# NodeFPGA.net
KiCad netlist of a schematic drawn in Altium Designer
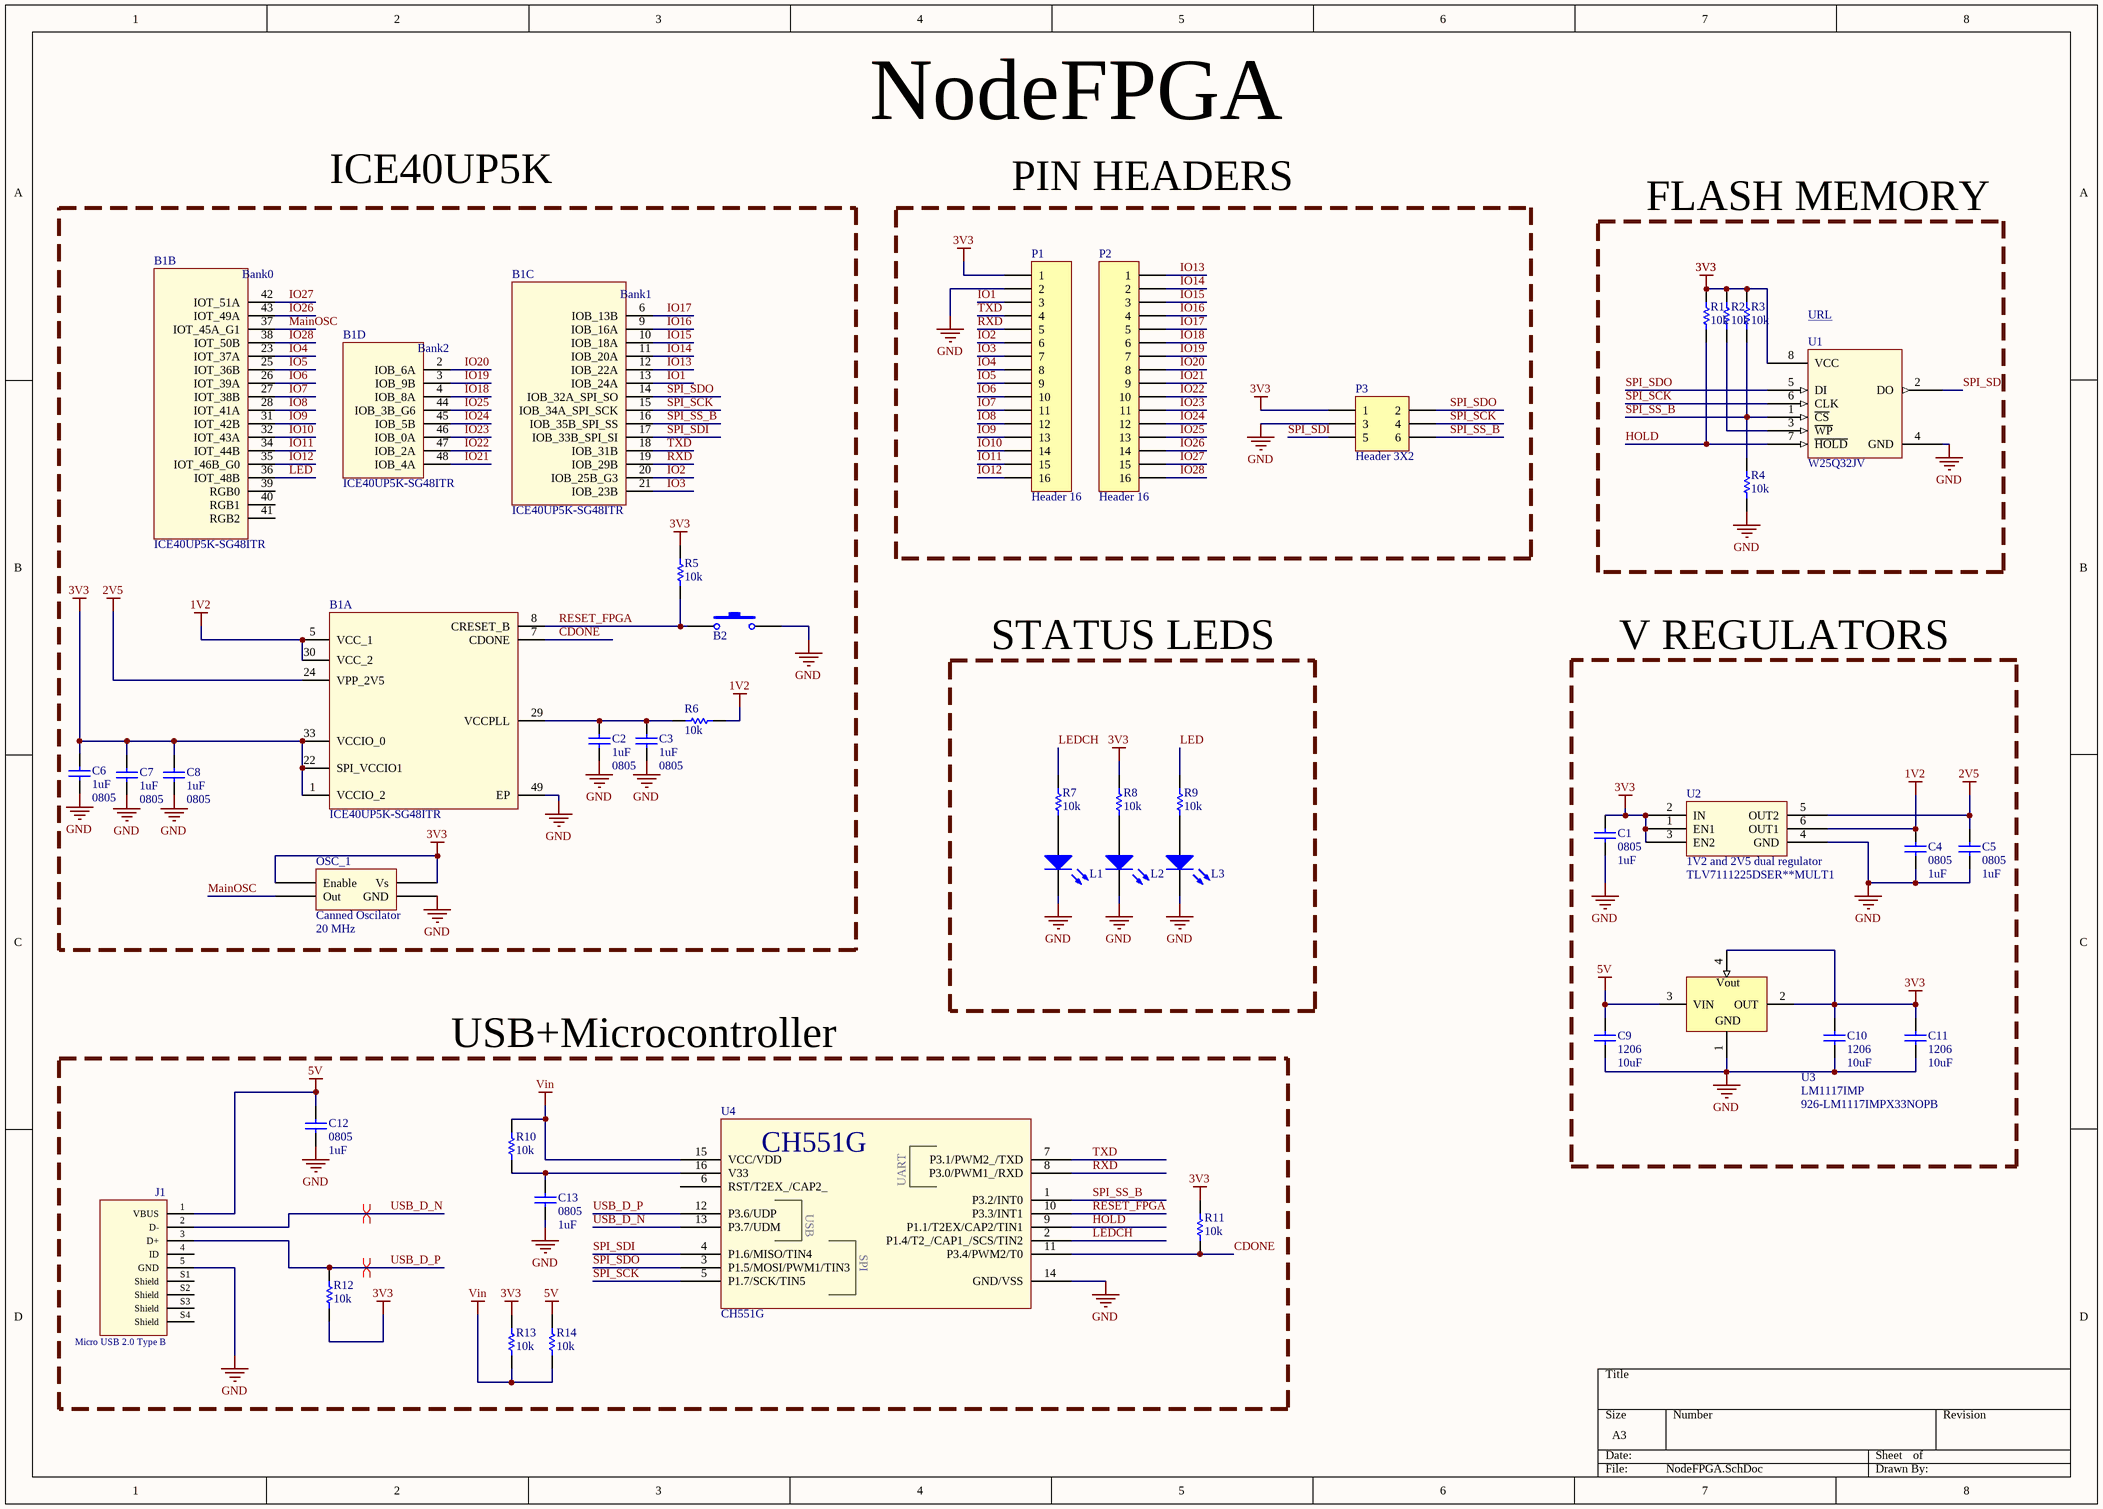
[diagram p0: NodeFPGA.SchDoc]

(export (version "E")
  (design (tool "Eeschema 10.0.6"))
  (components
    (comp (ref "B1")
      (value "ICE40UP5K-SG48ITR")
      (footprint "QFN50P700X700X100-49N-D")
      (description "FPGA - Field Programmable Gate Array iCE40-UltraPlus, 5280 LUTs, 1.2V")
      (fields (field (name "MOUSER PART NUMBER") "842-40UP5KSG48ITR"))
      (libsource (lib "ADCS") (part "ICE40UP5K-SG48ITR"))
    )
    (comp (ref "B2")
      (value "FSM6JH")
      (footprint "SMD_PUSHBUTTON_3x6x2mm5")
      (description "Button THT Switch")
      (libsource (lib "OpenFPGA") (part "FSM6JH"))
    )
    (comp (ref "C1")
      (value "0805")
      (footprint "0805")
      (description "Capacitor")
      (fields (field (name "ALTIUM_VALUE") "1uF"))
      (libsource (lib "GSATFPGA") (part "Capacitor_0805"))
    )
    (comp (ref "C2")
      (value "1uF")
      (footprint "0805")
      (description "Capacitor")
      (fields (field (name "PACKAGE") "0805") (field (name "Comment") "0805"))
      (libsource (lib "HeimdalLimiter") (part "Capacitor"))
    )
    (comp (ref "C3")
      (value "1uF")
      (footprint "0805")
      (description "Capacitor")
      (fields (field (name "PACKAGE") "0805") (field (name "Comment") "0805"))
      (libsource (lib "HeimdalLimiter") (part "Capacitor"))
    )
    (comp (ref "C4")
      (value "0805")
      (footprint "0805")
      (description "Capacitor")
      (fields (field (name "ALTIUM_VALUE") "1uF"))
      (libsource (lib "GSATFPGA") (part "Capacitor_0805"))
    )
    (comp (ref "C5")
      (value "0805")
      (footprint "0805")
      (description "Capacitor")
      (fields (field (name "ALTIUM_VALUE") "1uF"))
      (libsource (lib "GSATFPGA") (part "Capacitor_0805"))
    )
    (comp (ref "C6")
      (value "1uF")
      (footprint "0805")
      (description "Capacitor")
      (fields (field (name "PACKAGE") "0805") (field (name "Comment") "0805"))
      (libsource (lib "HeimdalLimiter") (part "Capacitor"))
    )
    (comp (ref "C7")
      (value "1uF")
      (footprint "0805")
      (description "Capacitor")
      (fields (field (name "PACKAGE") "0805") (field (name "Comment") "0805"))
      (libsource (lib "HeimdalLimiter") (part "Capacitor"))
    )
    (comp (ref "C8")
      (value "1uF")
      (footprint "0805")
      (description "Capacitor")
      (fields (field (name "PACKAGE") "0805") (field (name "Comment") "0805"))
      (libsource (lib "HeimdalLimiter") (part "Capacitor"))
    )
    (comp (ref "C9")
      (value "1206")
      (footprint "0805")
      (description "Capacitor")
      (fields (field (name "ALTIUM_VALUE") "10uF"))
      (libsource (lib "GSATFPGA") (part "Capacitor_1206"))
    )
    (comp (ref "C10")
      (value "1206")
      (footprint "0805")
      (description "Capacitor")
      (fields (field (name "ALTIUM_VALUE") "10uF"))
      (libsource (lib "GSATFPGA") (part "Capacitor_1206"))
    )
    (comp (ref "C11")
      (value "1206")
      (footprint "0805")
      (description "Capacitor")
      (fields (field (name "ALTIUM_VALUE") "10uF"))
      (libsource (lib "GSATFPGA") (part "Capacitor_1206"))
    )
    (comp (ref "C12")
      (value "0805")
      (footprint "0805")
      (description "Capacitor")
      (fields (field (name "ALTIUM_VALUE") "1uF"))
      (libsource (lib "GSATFPGA") (part "Capacitor_0805"))
    )
    (comp (ref "C13")
      (value "0805")
      (footprint "0805")
      (description "Capacitor")
      (fields (field (name "ALTIUM_VALUE") "1uF"))
      (libsource (lib "GSATFPGA") (part "Capacitor_0805"))
    )
    (comp (ref "J1")
      (value "Micro USB 2.0 Type B")
      (footprint "629105136821")
      (description "Micro USB 2.0 Type B Horizontal SMT 5 Contacts WR-COM")
      (fields (field (name "PART NUMBER") "629105136821") (field (name "PUBLISHER") "Wurth Elektronik"))
      (libsource (lib "GSATFPGA") (part "629105136821"))
    )
    (comp (ref "L1")
      (value "LED_SMD")
      (footprint "0805")
      (description "LED SMD")
      (libsource (lib "GSATFPGA") (part "LED_SMD"))
    )
    (comp (ref "L2")
      (value "LED_SMD")
      (footprint "0805")
      (description "LED SMD")
      (libsource (lib "GSATFPGA") (part "LED_SMD"))
    )
    (comp (ref "L3")
      (value "LED_SMD")
      (footprint "0805")
      (description "LED SMD")
      (libsource (lib "GSATFPGA") (part "LED_SMD"))
    )
    (comp (ref "OSC_1")
      (value "Canned Oscilator")
      (footprint "Canned Oscilator")
      (description "Canned Oscilator -LFSPXO019116BULK")
      (fields (field (name "ALTIUM_VALUE") "20 MHz"))
      (libsource (lib "GSATFPGA") (part "Canned Oscilator"))
    )
    (comp (ref "P1")
      (value "Header 16")
      (footprint "HDR1X16")
      (description "Header, 16-Pin")
      (fields (field (name "PUBLISHER") "Altium Limited"))
      (libsource (lib "") (part "Header 16_1"))
    )
    (comp (ref "P2")
      (value "Header 16")
      (footprint "HDR1X16")
      (description "Header, 16-Pin")
      (fields (field (name "PUBLISHER") "Altium Limited"))
      (libsource (lib "Miscellaneous Connectors") (part "Header 16"))
    )
    (comp (ref "P3")
      (value "Header 3X2")
      (footprint "HDR2X3")
      (description "Header, 3-Pin, Dual row")
      (fields (field (name "PUBLISHER") "Altium Limited"))
      (libsource (lib "Miscellaneous Connectors") (part "Header 3X2"))
    )
    (comp (ref "R1")
      (value "10k")
      (footprint "Resistencia 0603")
      (description "Resistor")
      (libsource (lib "OpenFPGA") (part "Resistor"))
    )
    (comp (ref "R2")
      (value "10k")
      (footprint "Resistencia 0603")
      (description "Resistor")
      (libsource (lib "OpenFPGA") (part "Resistor"))
    )
    (comp (ref "R3")
      (value "10k")
      (footprint "Resistencia 0603")
      (description "Resistor")
      (libsource (lib "OpenFPGA") (part "Resistor"))
    )
    (comp (ref "R4")
      (value "10k")
      (footprint "Resistencia 0603")
      (description "Resistor")
      (libsource (lib "OpenFPGA") (part "Resistor"))
    )
    (comp (ref "R5")
      (value "10k")
      (footprint "Resistencia 0603")
      (description "Resistor")
      (libsource (lib "OpenFPGA") (part "Resistor"))
    )
    (comp (ref "R6")
      (value "10k")
      (footprint "Resistencia 0603")
      (description "Resistor")
      (libsource (lib "OpenFPGA") (part "Resistor"))
    )
    (comp (ref "R7")
      (value "10k")
      (footprint "Resistencia 0603")
      (description "Resistor")
      (libsource (lib "OpenFPGA") (part "Resistor"))
    )
    (comp (ref "R8")
      (value "10k")
      (footprint "Resistencia 0603")
      (description "Resistor")
      (libsource (lib "OpenFPGA") (part "Resistor"))
    )
    (comp (ref "R9")
      (value "10k")
      (footprint "Resistencia 0603")
      (description "Resistor")
      (libsource (lib "OpenFPGA") (part "Resistor"))
    )
    (comp (ref "R10")
      (value "10k")
      (footprint "Resistencia 0603")
      (description "Resistor")
      (libsource (lib "OpenFPGA") (part "Resistor"))
    )
    (comp (ref "R11")
      (value "10k")
      (footprint "Resistencia 0603")
      (description "Resistor")
      (libsource (lib "OpenFPGA") (part "Resistor"))
    )
    (comp (ref "R12")
      (value "10k")
      (footprint "Resistencia 0603")
      (description "Resistor")
      (libsource (lib "OpenFPGA") (part "Resistor"))
    )
    (comp (ref "R13")
      (value "10k")
      (footprint "Resistencia 0603")
      (description "Resistor")
      (libsource (lib "OpenFPGA") (part "Resistor"))
    )
    (comp (ref "R14")
      (value "10k")
      (footprint "Resistencia 0603")
      (description "Resistor")
      (libsource (lib "OpenFPGA") (part "Resistor"))
    )
    (comp (ref "U1")
      (value "W25Q32JV")
      (footprint "W25Q32")
      (description "32M-BIT SERIAL FLASH MEMORY WITH DUAL AND QUAD SPI")
      (libsource (lib "GSATFPGA") (part "W25Q32JV"))
    )
    (comp (ref "U2")
      (value "1V2 and 2V5 dual regulator")
      (footprint "DSE 6")
      (fields (field (name "SUPPLIER PART NUMBER 1") "TLV7111225DSER**MULT1"))
      (libsource (lib "GSATFPGA") (part "TLV7111225DSER"))
    )
    (comp (ref "U3")
      (value "LM1117IMP")
      (footprint "SOT-223")
      (description "5V to 3.3V 800mA Low-Dropout Linear Regulator")
      (fields (field (name "SUPPLIER PART NUMBER 1") "926-LM1117IMPX33NOPB"))
      (libsource (lib "GSATFPGA") (part "LM1117IMP"))
    )
    (comp (ref "U4")
      (value "CH551G")
      (footprint "CH551")
      (description "Microcontroller wUSB support")
      (libsource (lib "GSATFPGA") (part "CH551G"))
    )
  )
  (nets
    (net (code "1") (name "/CDONE") (class "Default")
      (node (ref "B1") (pin "7") (pinfunction "CDONE_7") (pintype "passive"))
      (node (ref "R11") (pin "1") (pinfunction "1_1") (pintype "passive"))
      (node (ref "U4") (pin "11") (pinfunction "P3.4/PWM2/T0_11") (pintype "passive"))
    )
    (net (code "2") (name "/HOLD") (class "Default")
      (node (ref "R1") (pin "1") (pinfunction "1_1") (pintype "passive"))
      (node (ref "U1") (pin "7") (pinfunction "~{HOLD}_7") (pintype "input"))
      (node (ref "U4") (pin "9") (pinfunction "P1.1/T2EX/CAP2/TIN1_9") (pintype "passive"))
    )
    (net (code "3") (name "/IO1") (class "Default")
      (node (ref "B1") (pin "13") (pinfunction "IOB_24A_13") (pintype "passive"))
      (node (ref "P1") (pin "3") (pinfunction "3_3") (pintype "passive"))
    )
    (net (code "4") (name "/IO2") (class "Default")
      (node (ref "B1") (pin "20") (pinfunction "IOB_25B_G3_20") (pintype "passive"))
      (node (ref "P1") (pin "6") (pinfunction "6_6") (pintype "passive"))
    )
    (net (code "5") (name "/IO3") (class "Default")
      (node (ref "B1") (pin "21") (pinfunction "IOB_23B_21") (pintype "passive"))
      (node (ref "P1") (pin "7") (pinfunction "7_7") (pintype "passive"))
    )
    (net (code "6") (name "/IO4") (class "Default")
      (node (ref "B1") (pin "23") (pinfunction "IOT_37A_23") (pintype "passive"))
      (node (ref "P1") (pin "8") (pinfunction "8_8") (pintype "passive"))
    )
    (net (code "7") (name "/IO5") (class "Default")
      (node (ref "B1") (pin "25") (pinfunction "IOT_36B_25") (pintype "passive"))
      (node (ref "P1") (pin "9") (pinfunction "9_9") (pintype "passive"))
    )
    (net (code "8") (name "/IO6") (class "Default")
      (node (ref "B1") (pin "26") (pinfunction "IOT_39A_26") (pintype "passive"))
      (node (ref "P1") (pin "10") (pinfunction "10_10") (pintype "passive"))
    )
    (net (code "9") (name "/IO7") (class "Default")
      (node (ref "B1") (pin "27") (pinfunction "IOT_38B_27") (pintype "passive"))
      (node (ref "P1") (pin "11") (pinfunction "11_11") (pintype "passive"))
    )
    (net (code "10") (name "/IO8") (class "Default")
      (node (ref "B1") (pin "28") (pinfunction "IOT_41A_28") (pintype "passive"))
      (node (ref "P1") (pin "12") (pinfunction "12_12") (pintype "passive"))
    )
    (net (code "11") (name "/IO9") (class "Default")
      (node (ref "B1") (pin "31") (pinfunction "IOT_42B_31") (pintype "passive"))
      (node (ref "P1") (pin "13") (pinfunction "13_13") (pintype "passive"))
    )
    (net (code "12") (name "/IO10") (class "Default")
      (node (ref "B1") (pin "32") (pinfunction "IOT_43A_32") (pintype "passive"))
      (node (ref "P1") (pin "14") (pinfunction "14_14") (pintype "passive"))
    )
    (net (code "13") (name "/IO11") (class "Default")
      (node (ref "B1") (pin "34") (pinfunction "IOT_44B_34") (pintype "passive"))
      (node (ref "P1") (pin "15") (pinfunction "15_15") (pintype "passive"))
    )
    (net (code "14") (name "/IO12") (class "Default")
      (node (ref "B1") (pin "35") (pinfunction "IOT_46B_G0_35") (pintype "passive"))
      (node (ref "P1") (pin "16") (pinfunction "16_16") (pintype "passive"))
    )
    (net (code "15") (name "/IO13") (class "Default")
      (node (ref "B1") (pin "12") (pinfunction "IOB_22A_12") (pintype "passive"))
      (node (ref "P2") (pin "1") (pinfunction "1_1") (pintype "passive"))
    )
    (net (code "16") (name "/IO14") (class "Default")
      (node (ref "B1") (pin "11") (pinfunction "IOB_20A_11") (pintype "passive"))
      (node (ref "P2") (pin "2") (pinfunction "2_2") (pintype "passive"))
    )
    (net (code "17") (name "/IO15") (class "Default")
      (node (ref "B1") (pin "10") (pinfunction "IOB_18A_10") (pintype "passive"))
      (node (ref "P2") (pin "3") (pinfunction "3_3") (pintype "passive"))
    )
    (net (code "18") (name "/IO16") (class "Default")
      (node (ref "B1") (pin "9") (pinfunction "IOB_16A_9") (pintype "passive"))
      (node (ref "P2") (pin "4") (pinfunction "4_4") (pintype "passive"))
    )
    (net (code "19") (name "/IO17") (class "Default")
      (node (ref "B1") (pin "6") (pinfunction "IOB_13B_6") (pintype "passive"))
      (node (ref "P2") (pin "5") (pinfunction "5_5") (pintype "passive"))
    )
    (net (code "20") (name "/IO18") (class "Default")
      (node (ref "B1") (pin "4") (pinfunction "IOB_8A_4") (pintype "passive"))
      (node (ref "P2") (pin "6") (pinfunction "6_6") (pintype "passive"))
    )
    (net (code "21") (name "/IO19") (class "Default")
      (node (ref "B1") (pin "3") (pinfunction "IOB_9B_3") (pintype "passive"))
      (node (ref "P2") (pin "7") (pinfunction "7_7") (pintype "passive"))
    )
    (net (code "22") (name "/IO20") (class "Default")
      (node (ref "B1") (pin "2") (pinfunction "IOB_6A_2") (pintype "passive"))
      (node (ref "P2") (pin "8") (pinfunction "8_8") (pintype "passive"))
    )
    (net (code "23") (name "/IO21") (class "Default")
      (node (ref "B1") (pin "48") (pinfunction "IOB_4A_48") (pintype "passive"))
      (node (ref "P2") (pin "9") (pinfunction "9_9") (pintype "passive"))
    )
    (net (code "24") (name "/IO22") (class "Default")
      (node (ref "B1") (pin "47") (pinfunction "IOB_2A_47") (pintype "passive"))
      (node (ref "P2") (pin "10") (pinfunction "10_10") (pintype "passive"))
    )
    (net (code "25") (name "/IO23") (class "Default")
      (node (ref "B1") (pin "46") (pinfunction "IOB_0A_46") (pintype "passive"))
      (node (ref "P2") (pin "11") (pinfunction "11_11") (pintype "passive"))
    )
    (net (code "26") (name "/IO24") (class "Default")
      (node (ref "B1") (pin "45") (pinfunction "IOB_5B_45") (pintype "passive"))
      (node (ref "P2") (pin "12") (pinfunction "12_12") (pintype "passive"))
    )
    (net (code "27") (name "/IO25") (class "Default")
      (node (ref "B1") (pin "44") (pinfunction "IOB_3B_G6_44") (pintype "passive"))
      (node (ref "P2") (pin "13") (pinfunction "13_13") (pintype "passive"))
    )
    (net (code "28") (name "/IO26") (class "Default")
      (node (ref "B1") (pin "43") (pinfunction "IOT_49A_43") (pintype "passive"))
      (node (ref "P2") (pin "14") (pinfunction "14_14") (pintype "passive"))
    )
    (net (code "29") (name "/IO27") (class "Default")
      (node (ref "B1") (pin "42") (pinfunction "IOT_51A_42") (pintype "passive"))
      (node (ref "P2") (pin "15") (pinfunction "15_15") (pintype "passive"))
    )
    (net (code "30") (name "/IO28") (class "Default")
      (node (ref "B1") (pin "38") (pinfunction "IOT_50B_38") (pintype "passive"))
      (node (ref "P2") (pin "16") (pinfunction "16_16") (pintype "passive"))
    )
    (net (code "31") (name "/LED") (class "Default")
      (node (ref "B1") (pin "36") (pinfunction "IOT_48B_36") (pintype "passive"))
      (node (ref "R9") (pin "2") (pinfunction "2_2") (pintype "passive"))
    )
    (net (code "32") (name "/LEDCH") (class "Default")
      (node (ref "R7") (pin "2") (pinfunction "2_2") (pintype "passive"))
      (node (ref "U4") (pin "2") (pinfunction "P1.4/T2_/CAP1_/SCS/TIN2_2") (pintype "passive"))
    )
    (net (code "33") (name "/MainOSC") (class "Default")
      (node (ref "B1") (pin "37") (pinfunction "IOT_45A_G1_37") (pintype "passive"))
      (node (ref "OSC_1") (pin "3") (pinfunction "Out_3") (pintype "passive"))
    )
    (net (code "34") (name "/RESET_FPGA") (class "Default")
      (node (ref "B1") (pin "8") (pinfunction "CRESET_B_8") (pintype "passive"))
      (node (ref "B2") (pin "1") (pinfunction "1_1") (pintype "passive"))
      (node (ref "R5") (pin "1") (pinfunction "1_1") (pintype "passive"))
      (node (ref "U4") (pin "10") (pinfunction "P3.3/INT1_10") (pintype "passive"))
    )
    (net (code "35") (name "/RXD") (class "Default")
      (node (ref "B1") (pin "19") (pinfunction "IOB_29B_19") (pintype "passive"))
      (node (ref "P1") (pin "5") (pinfunction "5_5") (pintype "passive"))
      (node (ref "U4") (pin "8") (pinfunction "P3.0/PWM1_/RXD_8") (pintype "passive"))
    )
    (net (code "36") (name "/SPI_SCK") (class "Default")
      (node (ref "B1") (pin "15") (pinfunction "IOB_34A_SPI_SCK_15") (pintype "passive"))
      (node (ref "P3") (pin "4") (pinfunction "4_4") (pintype "passive"))
      (node (ref "U1") (pin "6") (pinfunction "CLK_6") (pintype "input"))
      (node (ref "U4") (pin "5") (pinfunction "P1.7/SCK/TIN5_5") (pintype "passive"))
    )
    (net (code "37") (name "/SPI_SDI") (class "Default")
      (node (ref "B1") (pin "17") (pinfunction "IOB_33B_SPI_SI_17") (pintype "passive"))
      (node (ref "P3") (pin "5") (pinfunction "5_5") (pintype "passive"))
      (node (ref "U1") (pin "2") (pinfunction "DO_2") (pintype "output"))
      (node (ref "U4") (pin "4") (pinfunction "P1.6/MISO/TIN4_4") (pintype "passive"))
    )
    (net (code "38") (name "/SPI_SDO") (class "Default")
      (node (ref "B1") (pin "14") (pinfunction "IOB_32A_SPI_SO_14") (pintype "passive"))
      (node (ref "P3") (pin "2") (pinfunction "2_2") (pintype "passive"))
      (node (ref "U1") (pin "5") (pinfunction "DI_5") (pintype "input"))
      (node (ref "U4") (pin "3") (pinfunction "P1.5/MOSI/PWM1/TIN3_3") (pintype "passive"))
    )
    (net (code "39") (name "/SPI_SS_B") (class "Default")
      (node (ref "B1") (pin "16") (pinfunction "IOB_35B_SPI_SS_16") (pintype "passive"))
      (node (ref "P3") (pin "6") (pinfunction "6_6") (pintype "passive"))
      (node (ref "R3") (pin "1") (pinfunction "1_1") (pintype "passive"))
      (node (ref "R4") (pin "2") (pinfunction "2_2") (pintype "passive"))
      (node (ref "U1") (pin "1") (pinfunction "~{CS}_1") (pintype "input"))
      (node (ref "U4") (pin "1") (pinfunction "P3.2/INT0_1") (pintype "passive"))
    )
    (net (code "40") (name "/TXD") (class "Default")
      (node (ref "B1") (pin "18") (pinfunction "IOB_31B_18") (pintype "passive"))
      (node (ref "P1") (pin "4") (pinfunction "4_4") (pintype "passive"))
      (node (ref "U4") (pin "7") (pinfunction "P3.1/PWM2_/TXD_7") (pintype "passive"))
    )
    (net (code "41") (name "/USB_D_N") (class "Default")
      (node (ref "J1") (pin "2") (pinfunction "D-_2") (pintype "passive"))
      (node (ref "U4") (pin "13") (pinfunction "P3.7/UDM_13") (pintype "passive"))
    )
    (net (code "42") (name "/USB_D_P") (class "Default")
      (node (ref "J1") (pin "3") (pinfunction "D+_3") (pintype "passive"))
      (node (ref "R12") (pin "1") (pinfunction "1_1") (pintype "passive"))
      (node (ref "U4") (pin "12") (pinfunction "P3.6/UDP_12") (pintype "passive"))
    )
    (net (code "43") (name "1V2") (class "Default")
      (node (ref "B1") (pin "30") (pinfunction "VCC_2_30") (pintype "passive"))
      (node (ref "B1") (pin "5") (pinfunction "VCC_1_5") (pintype "passive"))
      (node (ref "C4") (pin "1") (pinfunction "1_1") (pintype "passive"))
      (node (ref "R6") (pin "2") (pinfunction "2_2") (pintype "passive"))
      (node (ref "U2") (pin "6") (pinfunction "OUT1_6") (pintype "passive"))
    )
    (net (code "44") (name "2V5") (class "Default")
      (node (ref "B1") (pin "24") (pinfunction "VPP_2V5_24") (pintype "passive"))
      (node (ref "C5") (pin "1") (pinfunction "1_1") (pintype "passive"))
      (node (ref "U2") (pin "5") (pinfunction "OUT2_5") (pintype "passive"))
    )
    (net (code "45") (name "3V3") (class "Default")
      (node (ref "B1") (pin "1") (pinfunction "VCCIO_2_1") (pintype "passive"))
      (node (ref "B1") (pin "22") (pinfunction "SPI_VCCIO1_22") (pintype "passive"))
      (node (ref "B1") (pin "33") (pinfunction "VCCIO_0_33") (pintype "passive"))
      (node (ref "C1") (pin "1") (pinfunction "1_1") (pintype "passive"))
      (node (ref "C10") (pin "1") (pinfunction "1_1") (pintype "passive"))
      (node (ref "C11") (pin "1") (pinfunction "1_1") (pintype "passive"))
      (node (ref "C6") (pin "2") (pinfunction "2_2") (pintype "passive"))
      (node (ref "C7") (pin "2") (pinfunction "2_2") (pintype "passive"))
      (node (ref "C8") (pin "2") (pinfunction "2_2") (pintype "passive"))
      (node (ref "OSC_1") (pin "1") (pinfunction "Enable_1") (pintype "passive"))
      (node (ref "OSC_1") (pin "4") (pinfunction "Vs_4") (pintype "passive"))
      (node (ref "P1") (pin "1") (pinfunction "1_1") (pintype "passive"))
      (node (ref "P3") (pin "1") (pinfunction "1_1") (pintype "passive"))
      (node (ref "R1") (pin "2") (pinfunction "2_2") (pintype "passive"))
      (node (ref "R11") (pin "2") (pinfunction "2_2") (pintype "passive"))
      (node (ref "R12") (pin "2") (pinfunction "2_2") (pintype "passive"))
      (node (ref "R13") (pin "1") (pinfunction "1_1") (pintype "passive"))
      (node (ref "R2") (pin "2") (pinfunction "2_2") (pintype "passive"))
      (node (ref "R3") (pin "2") (pinfunction "2_2") (pintype "passive"))
      (node (ref "R5") (pin "2") (pinfunction "2_2") (pintype "passive"))
      (node (ref "R8") (pin "2") (pinfunction "2_2") (pintype "passive"))
      (node (ref "U1") (pin "8") (pinfunction "VCC_8") (pintype "power_in"))
      (node (ref "U2") (pin "1") (pinfunction "EN1_1") (pintype "passive"))
      (node (ref "U2") (pin "2") (pinfunction "IN_2") (pintype "passive"))
      (node (ref "U2") (pin "3") (pinfunction "EN2_3") (pintype "passive"))
      (node (ref "U3") (pin "2") (pinfunction "OUT_2") (pintype "passive"))
      (node (ref "U3") (pin "4") (pinfunction "Vout_4") (pintype "input"))
    )
    (net (code "46") (name "5V") (class "Default")
      (node (ref "C12") (pin "1") (pinfunction "1_1") (pintype "passive"))
      (node (ref "C9") (pin "1") (pinfunction "1_1") (pintype "passive"))
      (node (ref "J1") (pin "1") (pinfunction "VBUS_1") (pintype "passive"))
      (node (ref "R14") (pin "2") (pinfunction "2_2") (pintype "passive"))
      (node (ref "U3") (pin "3") (pinfunction "VIN_3") (pintype "power_in"))
    )
    (net (code "47") (name "GND") (class "Default")
      (node (ref "B1") (pin "49") (pinfunction "EP_49") (pintype "passive"))
      (node (ref "B2") (pin "2") (pinfunction "2_2") (pintype "passive"))
      (node (ref "C1") (pin "2") (pinfunction "2_2") (pintype "passive"))
      (node (ref "C10") (pin "2") (pinfunction "2_2") (pintype "passive"))
      (node (ref "C11") (pin "2") (pinfunction "2_2") (pintype "passive"))
      (node (ref "C12") (pin "2") (pinfunction "2_2") (pintype "passive"))
      (node (ref "C13") (pin "2") (pinfunction "2_2") (pintype "passive"))
      (node (ref "C2") (pin "1") (pinfunction "1_1") (pintype "passive"))
      (node (ref "C3") (pin "1") (pinfunction "1_1") (pintype "passive"))
      (node (ref "C4") (pin "2") (pinfunction "2_2") (pintype "passive"))
      (node (ref "C5") (pin "2") (pinfunction "2_2") (pintype "passive"))
      (node (ref "C6") (pin "1") (pinfunction "1_1") (pintype "passive"))
      (node (ref "C7") (pin "1") (pinfunction "1_1") (pintype "passive"))
      (node (ref "C8") (pin "1") (pinfunction "1_1") (pintype "passive"))
      (node (ref "C9") (pin "2") (pinfunction "2_2") (pintype "passive"))
      (node (ref "J1") (pin "5") (pinfunction "GND_5") (pintype "passive"))
      (node (ref "L1") (pin "2") (pinfunction "K_2") (pintype "passive"))
      (node (ref "L2") (pin "2") (pinfunction "K_2") (pintype "passive"))
      (node (ref "L3") (pin "2") (pinfunction "K_2") (pintype "passive"))
      (node (ref "OSC_1") (pin "2") (pinfunction "GND_2") (pintype "passive"))
      (node (ref "P1") (pin "2") (pinfunction "2_2") (pintype "passive"))
      (node (ref "P3") (pin "3") (pinfunction "3_3") (pintype "passive"))
      (node (ref "R4") (pin "1") (pinfunction "1_1") (pintype "passive"))
      (node (ref "U1") (pin "4") (pinfunction "GND_4") (pintype "power_in"))
      (node (ref "U2") (pin "4") (pinfunction "GND_4") (pintype "passive"))
      (node (ref "U3") (pin "1") (pinfunction "GND_1") (pintype "power_in"))
      (node (ref "U4") (pin "14") (pinfunction "GND/VSS_14") (pintype "passive"))
    )
    (net (code "48") (name "Net-(B1A-VCCPLL)") (class "Default")
      (node (ref "B1") (pin "29") (pinfunction "VCCPLL_29") (pintype "passive"))
      (node (ref "C2") (pin "2") (pinfunction "2_2") (pintype "passive"))
      (node (ref "C3") (pin "2") (pinfunction "2_2") (pintype "passive"))
      (node (ref "R6") (pin "1") (pinfunction "1_1") (pintype "passive"))
    )
    (net (code "49") (name "Net-(L1-A)") (class "Default")
      (node (ref "L1") (pin "1") (pinfunction "A_1") (pintype "passive"))
      (node (ref "R7") (pin "1") (pinfunction "1_1") (pintype "passive"))
    )
    (net (code "50") (name "Net-(L2-A)") (class "Default")
      (node (ref "L2") (pin "1") (pinfunction "A_1") (pintype "passive"))
      (node (ref "R8") (pin "1") (pinfunction "1_1") (pintype "passive"))
    )
    (net (code "51") (name "Net-(L3-A)") (class "Default")
      (node (ref "L3") (pin "1") (pinfunction "A_1") (pintype "passive"))
      (node (ref "R9") (pin "1") (pinfunction "1_1") (pintype "passive"))
    )
    (net (code "52") (name "Net-(U1-~{WP})") (class "Default")
      (node (ref "R2") (pin "1") (pinfunction "1_1") (pintype "passive"))
      (node (ref "U1") (pin "3") (pinfunction "~{WP}_3") (pintype "input"))
    )
    (net (code "53") (name "Net-(U4-V33)") (class "Default")
      (node (ref "C13") (pin "1") (pinfunction "1_1") (pintype "passive"))
      (node (ref "R10") (pin "2") (pinfunction "2_2") (pintype "passive"))
      (node (ref "U4") (pin "16") (pinfunction "V33_16") (pintype "passive"))
    )
    (net (code "54") (name "Vin") (class "Default")
      (node (ref "R10") (pin "1") (pinfunction "1_1") (pintype "passive"))
      (node (ref "R13") (pin "2") (pinfunction "2_2") (pintype "passive"))
      (node (ref "R14") (pin "1") (pinfunction "1_1") (pintype "passive"))
      (node (ref "U4") (pin "15") (pinfunction "VCC/VDD_15") (pintype "passive"))
    )
    (net (code "55") (name "unconnected-(B1B-RGB0-Pad39)") (class "Default")
      (node (ref "B1") (pin "39") (pinfunction "RGB0_39") (pintype "passive"))
    )
    (net (code "56") (name "unconnected-(B1B-RGB1-Pad40)") (class "Default")
      (node (ref "B1") (pin "40") (pinfunction "RGB1_40") (pintype "passive"))
    )
    (net (code "57") (name "unconnected-(B1B-RGB2-Pad41)") (class "Default")
      (node (ref "B1") (pin "41") (pinfunction "RGB2_41") (pintype "passive"))
    )
    (net (code "58") (name "unconnected-(J1-ID-Pad4)") (class "Default")
      (node (ref "J1") (pin "4") (pinfunction "ID_4") (pintype "passive"))
    )
    (net (code "59") (name "unconnected-(J1-Shield-PadS1)") (class "Default")
      (node (ref "J1") (pin "S1") (pinfunction "Shield_S1") (pintype "passive"))
    )
    (net (code "60") (name "unconnected-(J1-Shield-PadS2)") (class "Default")
      (node (ref "J1") (pin "S2") (pinfunction "Shield_S2") (pintype "passive"))
    )
    (net (code "61") (name "unconnected-(J1-Shield-PadS3)") (class "Default")
      (node (ref "J1") (pin "S3") (pinfunction "Shield_S3") (pintype "passive"))
    )
    (net (code "62") (name "unconnected-(J1-Shield-PadS4)") (class "Default")
      (node (ref "J1") (pin "S4") (pinfunction "Shield_S4") (pintype "passive"))
    )
    (net (code "63") (name "unconnected-(U4-RST{slash}T2EX_{slash}CAP2_-Pad6)") (class "Default")
      (node (ref "U4") (pin "6") (pinfunction "RST/T2EX_/CAP2__6") (pintype "passive"))
    )
  )
)
